# board_lt3086.net
KiCad netlist of a schematic drawn in EAGLE
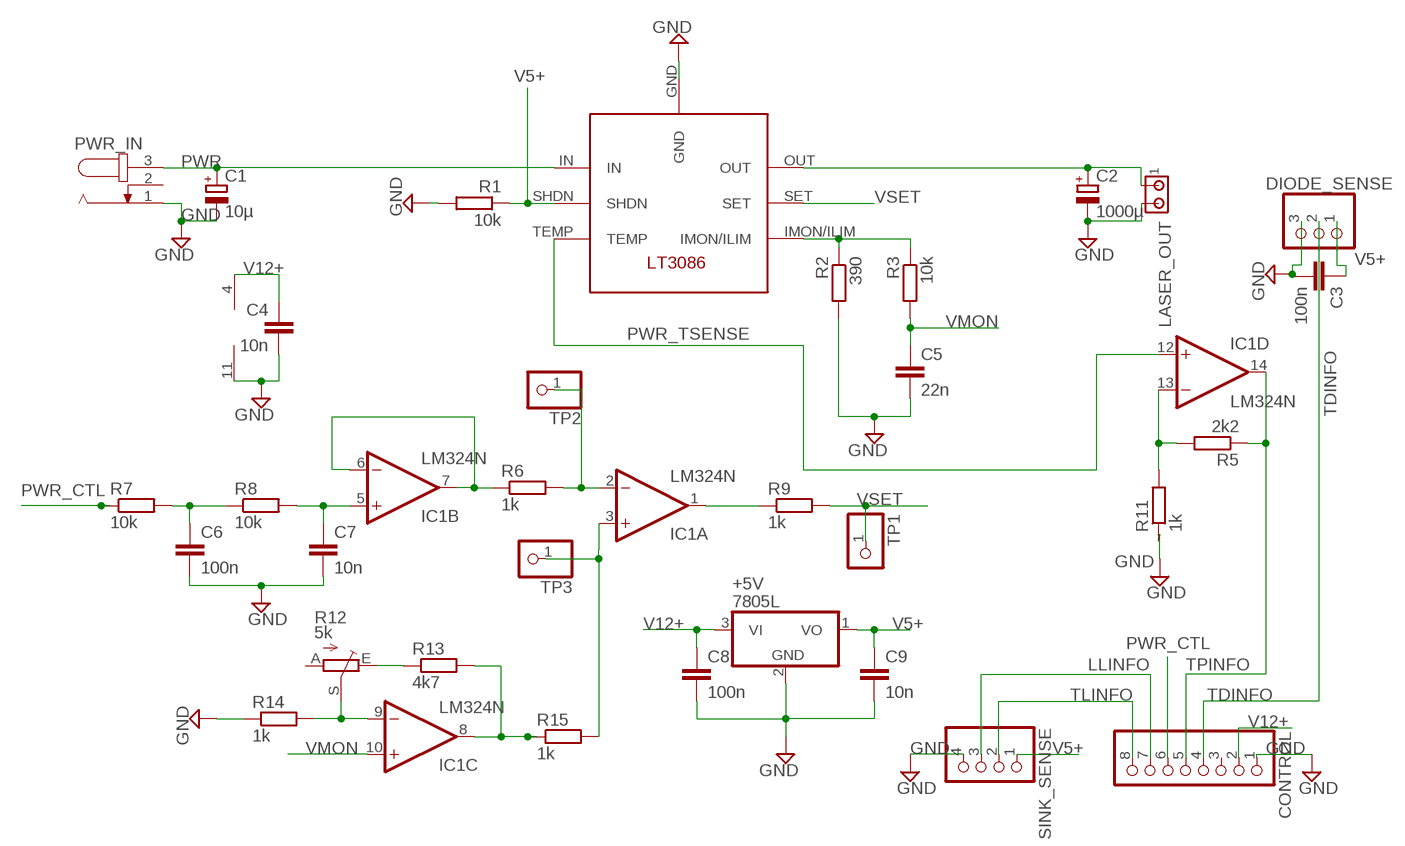
[diagram p0: schematic, sheet 1]

(export (version "E")
  (design (tool "Eeschema 10.0.6"))
  (components
    (comp (ref "+5V")
      (value "7805L")
      (footprint "eagle-import:TO92")
      (libsource (lib "eagle-import") (part "78L05"))
    )
    (comp (ref "C1")
      (value "10µ")
      (footprint "eagle-import:E2,5-7")
      (libsource (lib "eagle-import") (part "CPOL-EUE2.5-7"))
    )
    (comp (ref "C2")
      (value "1000µ")
      (footprint "eagle-import:E3,5-10")
      (libsource (lib "eagle-import") (part "CPOL-EUE3.5-10"))
    )
    (comp (ref "C3")
      (value "100n")
      (footprint "eagle-import:C050-035X075")
      (libsource (lib "eagle-import") (part "C-EU050-035X075"))
    )
    (comp (ref "C4")
      (value "10n")
      (footprint "eagle-import:C050-024X044")
      (libsource (lib "eagle-import") (part "C-EU050-024X044"))
    )
    (comp (ref "C5")
      (value "22n")
      (footprint "eagle-import:C050-024X044")
      (libsource (lib "eagle-import") (part "C-EU050-024X044"))
    )
    (comp (ref "C6")
      (value "100n")
      (footprint "eagle-import:C050-035X075")
      (libsource (lib "eagle-import") (part "C-EU050-035X075"))
    )
    (comp (ref "C7")
      (value "10n")
      (footprint "eagle-import:C050-024X044")
      (libsource (lib "eagle-import") (part "C-EU050-024X044"))
    )
    (comp (ref "C8")
      (value "100n")
      (footprint "eagle-import:C050-035X075")
      (libsource (lib "eagle-import") (part "C-EU050-035X075"))
    )
    (comp (ref "C9")
      (value "10n")
      (footprint "eagle-import:C050-024X044")
      (libsource (lib "eagle-import") (part "C-EU050-024X044"))
    )
    (comp (ref "CONTROL")
      (value "PINHD-1X8")
      (footprint "eagle-import:1X08")
      (libsource (lib "eagle-import") (part "PINHD-1X8"))
    )
    (comp (ref "DIODE_SENSE")
      (value "PINHD-1X3")
      (footprint "eagle-import:1X03")
      (libsource (lib "eagle-import") (part "PINHD-1X3"))
    )
    (comp (ref "IC1")
      (value "LM324N")
      (footprint "eagle-import:DIL14")
      (libsource (lib "eagle-import") (part "LM324N"))
    )
    (comp (ref "LASER_OUT")
      (value "350428-1")
      (footprint "eagle-import:350428-1")
      (libsource (lib "eagle-import") (part "350428-1"))
    )
    (comp (ref "PWR_CTRL")
      (value "LT3086")
      (footprint "eagle-import:LT3086-T7")
      (libsource (lib "eagle-import") (part "LT3086"))
    )
    (comp (ref "PWR_IN")
      (value "JACK-PLUG0")
      (footprint "eagle-import:SPC4077")
      (libsource (lib "eagle-import") (part "JACK-PLUG0"))
    )
    (comp (ref "R1")
      (value "10k")
      (footprint "eagle-import:0207_10")
      (libsource (lib "eagle-import") (part "R-EU_0207/10"))
    )
    (comp (ref "R2")
      (value "390")
      (footprint "eagle-import:0207_10")
      (libsource (lib "eagle-import") (part "R-EU_0207/10"))
    )
    (comp (ref "R3")
      (value "10k")
      (footprint "eagle-import:0207_10")
      (libsource (lib "eagle-import") (part "R-EU_0207/10"))
    )
    (comp (ref "R5")
      (value "2k2")
      (footprint "eagle-import:0207_10")
      (libsource (lib "eagle-import") (part "R-EU_0207/10"))
    )
    (comp (ref "R6")
      (value "1k")
      (footprint "eagle-import:0207_10")
      (libsource (lib "eagle-import") (part "R-EU_0207/10"))
    )
    (comp (ref "R7")
      (value "10k")
      (footprint "eagle-import:0207_10")
      (libsource (lib "eagle-import") (part "R-EU_0207/10"))
    )
    (comp (ref "R8")
      (value "10k")
      (footprint "eagle-import:0207_10")
      (libsource (lib "eagle-import") (part "R-EU_0207/10"))
    )
    (comp (ref "R9")
      (value "1k")
      (footprint "eagle-import:0207_10")
      (libsource (lib "eagle-import") (part "R-EU_0207/10"))
    )
    (comp (ref "R11")
      (value "1k")
      (footprint "eagle-import:0207_10")
      (libsource (lib "eagle-import") (part "R-EU_0207/10"))
    )
    (comp (ref "R12")
      (value "5k")
      (footprint "eagle-import:CA9V")
      (libsource (lib "eagle-import") (part "TRIM_EU-CA9V"))
    )
    (comp (ref "R13")
      (value "4k7")
      (footprint "eagle-import:0207_10")
      (libsource (lib "eagle-import") (part "R-EU_0207/10"))
    )
    (comp (ref "R14")
      (value "1k")
      (footprint "eagle-import:0207_10")
      (libsource (lib "eagle-import") (part "R-EU_0207/10"))
    )
    (comp (ref "R15")
      (value "1k")
      (footprint "eagle-import:0207_10")
      (libsource (lib "eagle-import") (part "R-EU_0207/10"))
    )
    (comp (ref "SINK_SENSE")
      (value "PINHD-1X4")
      (footprint "eagle-import:1X04")
      (libsource (lib "eagle-import") (part "PINHD-1X4"))
    )
    (comp (ref "TP1")
      (value "PINHD-1X1")
      (footprint "eagle-import:1X01")
      (libsource (lib "eagle-import") (part "PINHD-1X1"))
    )
    (comp (ref "TP2")
      (value "PINHD-1X1")
      (footprint "eagle-import:1X01")
      (libsource (lib "eagle-import") (part "PINHD-1X1"))
    )
    (comp (ref "TP3")
      (value "PINHD-1X1")
      (footprint "eagle-import:1X01")
      (libsource (lib "eagle-import") (part "PINHD-1X1"))
    )
  )
  (nets
    (net (code "1") (name "/LLINFO") (class "Default")
      (node (ref "CONTROL") (pin "7") (pinfunction "7_7") (pintype "passive"))
      (node (ref "SINK_SENSE") (pin "3") (pinfunction "3_3") (pintype "passive"))
    )
    (net (code "2") (name "/PWR") (class "Default")
      (node (ref "C1") (pin "+") (pinfunction "+_+") (pintype "passive"))
      (node (ref "PWR_CTRL") (pin "IN") (pinfunction "IN_IN") (pintype "bidirectional"))
      (node (ref "PWR_IN") (pin "3") (pinfunction "3_3") (pintype "passive"))
    )
    (net (code "3") (name "/PWR_CTL") (class "Default")
      (node (ref "CONTROL") (pin "6") (pinfunction "6_6") (pintype "passive"))
      (node (ref "R7") (pin "1") (pinfunction "1_1") (pintype "passive"))
    )
    (net (code "4") (name "/PWR_TSENSE") (class "Default")
      (node (ref "IC1") (pin "12") (pinfunction "+IN_12") (pintype "input"))
      (node (ref "PWR_CTRL") (pin "TEMP") (pinfunction "TEMP_TEMP") (pintype "bidirectional"))
    )
    (net (code "5") (name "/TDINFO") (class "Default")
      (node (ref "CONTROL") (pin "4") (pinfunction "4_4") (pintype "passive"))
      (node (ref "DIODE_SENSE") (pin "2") (pinfunction "2_2") (pintype "passive"))
    )
    (net (code "6") (name "/TLINFO") (class "Default")
      (node (ref "CONTROL") (pin "8") (pinfunction "8_8") (pintype "passive"))
      (node (ref "SINK_SENSE") (pin "2") (pinfunction "2_2") (pintype "passive"))
    )
    (net (code "7") (name "/TPINFO") (class "Default")
      (node (ref "CONTROL") (pin "5") (pinfunction "5_5") (pintype "passive"))
      (node (ref "IC1") (pin "14") (pinfunction "OUT_14") (pintype "output"))
      (node (ref "R5") (pin "1") (pinfunction "1_1") (pintype "passive"))
    )
    (net (code "8") (name "/V5+") (class "Default")
      (node (ref "+5V") (pin "1") (pinfunction "VO_1") (pintype "passive"))
      (node (ref "C3") (pin "1") (pinfunction "1_1") (pintype "passive"))
      (node (ref "C9") (pin "1") (pinfunction "1_1") (pintype "passive"))
      (node (ref "DIODE_SENSE") (pin "1") (pinfunction "1_1") (pintype "passive"))
      (node (ref "PWR_CTRL") (pin "SHDN") (pinfunction "SHDN_SHDN") (pintype "bidirectional"))
      (node (ref "R1") (pin "1") (pinfunction "1_1") (pintype "passive"))
      (node (ref "SINK_SENSE") (pin "1") (pinfunction "1_1") (pintype "passive"))
    )
    (net (code "9") (name "/V12+") (class "Default")
      (node (ref "+5V") (pin "3") (pinfunction "VI_3") (pintype "input"))
      (node (ref "C4") (pin "1") (pinfunction "1_1") (pintype "passive"))
      (node (ref "C8") (pin "1") (pinfunction "1_1") (pintype "passive"))
      (node (ref "CONTROL") (pin "2") (pinfunction "2_2") (pintype "passive"))
      (node (ref "IC1") (pin "4") (pinfunction "V+_4") (pintype "power_in"))
    )
    (net (code "10") (name "/VMON") (class "Default")
      (node (ref "C5") (pin "1") (pinfunction "1_1") (pintype "passive"))
      (node (ref "IC1") (pin "10") (pinfunction "+IN_10") (pintype "input"))
      (node (ref "R3") (pin "2") (pinfunction "2_2") (pintype "passive"))
    )
    (net (code "11") (name "/VSET") (class "Default")
      (node (ref "PWR_CTRL") (pin "SET") (pinfunction "SET_SET") (pintype "bidirectional"))
      (node (ref "R9") (pin "2") (pinfunction "2_2") (pintype "passive"))
      (node (ref "TP1") (pin "1") (pinfunction "1_1") (pintype "passive"))
    )
    (net (code "12") (name "GND") (class "Default")
      (node (ref "+5V") (pin "2") (pinfunction "GND_2") (pintype "passive"))
      (node (ref "C1") (pin "-") (pinfunction "-_-") (pintype "passive"))
      (node (ref "C2") (pin "-") (pinfunction "-_-") (pintype "passive"))
      (node (ref "C3") (pin "2") (pinfunction "2_2") (pintype "passive"))
      (node (ref "C4") (pin "2") (pinfunction "2_2") (pintype "passive"))
      (node (ref "C5") (pin "2") (pinfunction "2_2") (pintype "passive"))
      (node (ref "C6") (pin "2") (pinfunction "2_2") (pintype "passive"))
      (node (ref "C7") (pin "2") (pinfunction "2_2") (pintype "passive"))
      (node (ref "C8") (pin "2") (pinfunction "2_2") (pintype "passive"))
      (node (ref "C9") (pin "2") (pinfunction "2_2") (pintype "passive"))
      (node (ref "CONTROL") (pin "1") (pinfunction "1_1") (pintype "passive"))
      (node (ref "DIODE_SENSE") (pin "3") (pinfunction "3_3") (pintype "passive"))
      (node (ref "IC1") (pin "11") (pinfunction "V-_11") (pintype "power_in"))
      (node (ref "LASER_OUT") (pin "2") (pinfunction "2_2") (pintype "passive"))
      (node (ref "PWR_CTRL") (pin "GND") (pinfunction "GND_GND") (pintype "bidirectional"))
      (node (ref "PWR_IN") (pin "1") (pinfunction "1_1") (pintype "passive"))
      (node (ref "R1") (pin "2") (pinfunction "2_2") (pintype "passive"))
      (node (ref "R11") (pin "1") (pinfunction "1_1") (pintype "passive"))
      (node (ref "R14") (pin "1") (pinfunction "1_1") (pintype "passive"))
      (node (ref "R2") (pin "2") (pinfunction "2_2") (pintype "passive"))
      (node (ref "SINK_SENSE") (pin "4") (pinfunction "4_4") (pintype "passive"))
    )
    (net (code "13") (name "Net-(C2-Pad+)") (class "Default")
      (node (ref "C2") (pin "+") (pinfunction "+_+") (pintype "passive"))
      (node (ref "LASER_OUT") (pin "1") (pinfunction "1_1") (pintype "passive"))
      (node (ref "PWR_CTRL") (pin "OUT") (pinfunction "OUT_OUT") (pintype "bidirectional"))
    )
    (net (code "14") (name "Net-(C6-Pad1)") (class "Default")
      (node (ref "C6") (pin "1") (pinfunction "1_1") (pintype "passive"))
      (node (ref "R7") (pin "2") (pinfunction "2_2") (pintype "passive"))
      (node (ref "R8") (pin "1") (pinfunction "1_1") (pintype "passive"))
    )
    (net (code "15") (name "Net-(IC1A-+IN)") (class "Default")
      (node (ref "IC1") (pin "3") (pinfunction "+IN_3") (pintype "input"))
      (node (ref "R15") (pin "2") (pinfunction "2_2") (pintype "passive"))
      (node (ref "TP3") (pin "1") (pinfunction "1_1") (pintype "passive"))
    )
    (net (code "16") (name "Net-(IC1A--IN)") (class "Default")
      (node (ref "IC1") (pin "2") (pinfunction "-IN_2") (pintype "input"))
      (node (ref "R6") (pin "2") (pinfunction "2_2") (pintype "passive"))
      (node (ref "TP2") (pin "1") (pinfunction "1_1") (pintype "passive"))
    )
    (net (code "17") (name "Net-(IC1A-OUT)") (class "Default")
      (node (ref "IC1") (pin "1") (pinfunction "OUT_1") (pintype "output"))
      (node (ref "R9") (pin "1") (pinfunction "1_1") (pintype "passive"))
    )
    (net (code "18") (name "Net-(IC1B-+IN)") (class "Default")
      (node (ref "C7") (pin "1") (pinfunction "1_1") (pintype "passive"))
      (node (ref "IC1") (pin "5") (pinfunction "+IN_5") (pintype "input"))
      (node (ref "R8") (pin "2") (pinfunction "2_2") (pintype "passive"))
    )
    (net (code "19") (name "Net-(IC1B--IN)") (class "Default")
      (node (ref "IC1") (pin "6") (pinfunction "-IN_6") (pintype "input"))
      (node (ref "IC1") (pin "7") (pinfunction "OUT_7") (pintype "output"))
      (node (ref "R6") (pin "1") (pinfunction "1_1") (pintype "passive"))
    )
    (net (code "20") (name "Net-(IC1C--IN)") (class "Default")
      (node (ref "IC1") (pin "9") (pinfunction "-IN_9") (pintype "input"))
      (node (ref "R12") (pin "S") (pinfunction "S_S") (pintype "passive"))
      (node (ref "R14") (pin "2") (pinfunction "2_2") (pintype "passive"))
    )
    (net (code "21") (name "Net-(IC1C-OUT)") (class "Default")
      (node (ref "IC1") (pin "8") (pinfunction "OUT_8") (pintype "output"))
      (node (ref "R13") (pin "2") (pinfunction "2_2") (pintype "passive"))
      (node (ref "R15") (pin "1") (pinfunction "1_1") (pintype "passive"))
    )
    (net (code "22") (name "Net-(IC1D--IN)") (class "Default")
      (node (ref "IC1") (pin "13") (pinfunction "-IN_13") (pintype "input"))
      (node (ref "R11") (pin "2") (pinfunction "2_2") (pintype "passive"))
      (node (ref "R5") (pin "2") (pinfunction "2_2") (pintype "passive"))
    )
    (net (code "23") (name "Net-(PWR_CTRL-PadIMON{slash}ILIM)") (class "Default")
      (node (ref "PWR_CTRL") (pin "IMON/ILIM") (pinfunction "IMON/ILIM_IMON/ILIM") (pintype "bidirectional"))
      (node (ref "R2") (pin "1") (pinfunction "1_1") (pintype "passive"))
      (node (ref "R3") (pin "1") (pinfunction "1_1") (pintype "passive"))
    )
    (net (code "24") (name "Net-(R12-PadE)") (class "Default")
      (node (ref "R12") (pin "E") (pinfunction "E_E") (pintype "passive"))
      (node (ref "R13") (pin "1") (pinfunction "1_1") (pintype "passive"))
    )
    (net (code "25") (name "unconnected-(CONTROL-Pad3)") (class "Default")
      (node (ref "CONTROL") (pin "3") (pinfunction "3_3") (pintype "passive"))
    )
    (net (code "26") (name "unconnected-(PWR_IN-Pad2)") (class "Default")
      (node (ref "PWR_IN") (pin "2") (pinfunction "2_2") (pintype "passive"))
    )
    (net (code "27") (name "unconnected-(R12-PadA)") (class "Default")
      (node (ref "R12") (pin "A") (pinfunction "A_A") (pintype "passive"))
    )
  )
)
